# powermeter.net
KiCad netlist of a schematic drawn in EAGLE
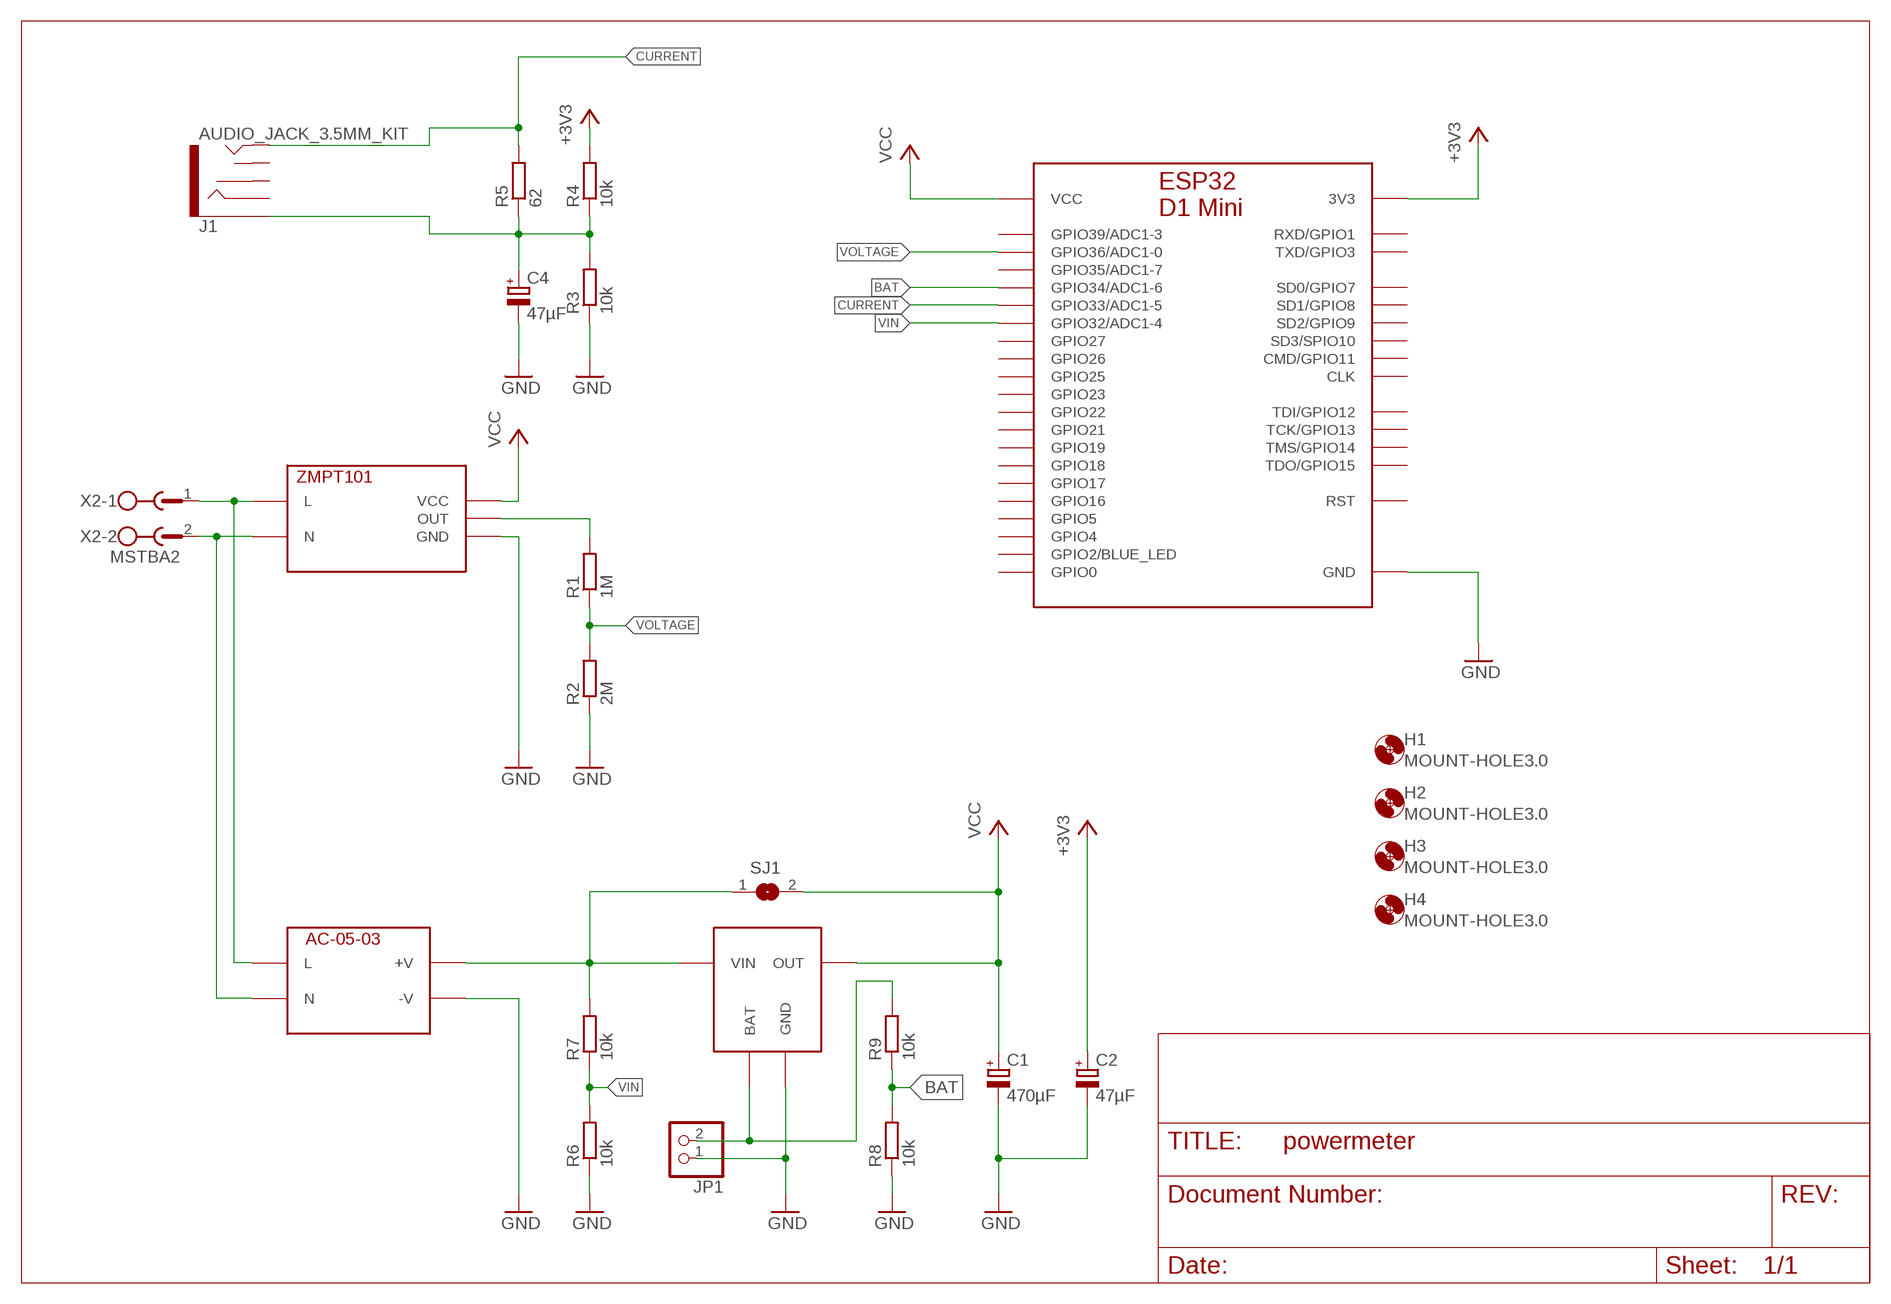
[diagram p0: schematic, sheet 1]

(export (version "E")
  (design (tool "Eeschema 10.0.6"))
  (components
    (comp (ref "C1")
      (value "470µF")
      (footprint "eagle-import:E5-8,5")
      (libsource (lib "eagle-import") (part "CPOL-EUE5-8.5"))
    )
    (comp (ref "C2")
      (value "47µF")
      (footprint "eagle-import:E2,5-5")
      (libsource (lib "eagle-import") (part "CPOL-EUE2.5-5"))
    )
    (comp (ref "C4")
      (value "47µF")
      (footprint "eagle-import:E2,5-5")
      (libsource (lib "eagle-import") (part "CPOL-EUE2.5-5"))
    )
    (comp (ref "H1")
      (value "MOUNT-HOLE3.0")
      (footprint "eagle-import:3,0")
      (libsource (lib "eagle-import") (part "MOUNT-HOLE3.0"))
    )
    (comp (ref "H2")
      (value "MOUNT-HOLE3.0")
      (footprint "eagle-import:3,0")
      (libsource (lib "eagle-import") (part "MOUNT-HOLE3.0"))
    )
    (comp (ref "H3")
      (value "MOUNT-HOLE3.0")
      (footprint "eagle-import:3,0")
      (libsource (lib "eagle-import") (part "MOUNT-HOLE3.0"))
    )
    (comp (ref "H4")
      (value "MOUNT-HOLE3.0")
      (footprint "eagle-import:3,0")
      (libsource (lib "eagle-import") (part "MOUNT-HOLE3.0"))
    )
    (comp (ref "J1")
      (value "AUDIO_JACK_3.5MM_KIT")
      (footprint "eagle-import:AUDIO-JACK-KIT")
      (libsource (lib "eagle-import") (part "AUDIO_JACK_3.5MM_KIT"))
    )
    (comp (ref "JP1")
      (value "PINHD-1X2")
      (footprint "eagle-import:1X02")
      (libsource (lib "eagle-import") (part "PINHD-1X2"))
    )
    (comp (ref "R1")
      (value "1M")
      (footprint "eagle-import:0204_7")
      (libsource (lib "eagle-import") (part "R-EU_0204/7"))
    )
    (comp (ref "R2")
      (value "2M")
      (footprint "eagle-import:0204_7")
      (libsource (lib "eagle-import") (part "R-EU_0204/7"))
    )
    (comp (ref "R3")
      (value "10k")
      (footprint "eagle-import:0204_7")
      (libsource (lib "eagle-import") (part "R-EU_0204/7"))
    )
    (comp (ref "R4")
      (value "10k")
      (footprint "eagle-import:0204_7")
      (libsource (lib "eagle-import") (part "R-EU_0204/7"))
    )
    (comp (ref "R5")
      (value "62")
      (footprint "eagle-import:0204_7")
      (libsource (lib "eagle-import") (part "R-EU_0204/7"))
    )
    (comp (ref "R6")
      (value "10k")
      (footprint "eagle-import:0204_7")
      (libsource (lib "eagle-import") (part "R-EU_0204/7"))
    )
    (comp (ref "R7")
      (value "10k")
      (footprint "eagle-import:0204_7")
      (libsource (lib "eagle-import") (part "R-EU_0204/7"))
    )
    (comp (ref "R8")
      (value "10k")
      (footprint "eagle-import:0204_7")
      (libsource (lib "eagle-import") (part "R-EU_0204/7"))
    )
    (comp (ref "R9")
      (value "10k")
      (footprint "eagle-import:0204_7")
      (libsource (lib "eagle-import") (part "R-EU_0204/7"))
    )
    (comp (ref "SJ1") (value "SJ") (footprint "eagle-import:SJ") (libsource (lib "eagle-import") (part "SJ")))
    (comp (ref "U$1")
      (value "ZMPT101")
      (footprint "eagle-import:ZMPT101")
      (libsource (lib "eagle-import") (part "ZMPT101"))
    )
    (comp (ref "U$2")
      (value "AC-05-03")
      (footprint "eagle-import:AC-05-03")
      (libsource (lib "eagle-import") (part "AC-05-03"))
    )
    (comp (ref "U$3")
      (value "MINI-UPS-S")
      (footprint "eagle-import:MINI-UPS-S")
      (libsource (lib "eagle-import") (part "MINI-UPS-S"))
    )
    (comp (ref "U1")
      (value "ESP32D1MINI")
      (footprint "eagle-import:ESP32D1MINI")
      (libsource (lib "eagle-import") (part "ESP32D1MINI"))
    )
    (comp (ref "X2")
      (value "MSTBA2")
      (footprint "eagle-import:MSTBA2")
      (fields (field (name "MF") "FARNELL") (field (name "MPN") "1757242"))
      (libsource (lib "eagle-import") (part "MSTBA2"))
    )
  )
  (nets
    (net (code "1") (name "+3V3") (class "Default")
      (node (ref "C2") (pin "+") (pinfunction "+_+") (pintype "passive"))
      (node (ref "R4") (pin "2") (pinfunction "2_2") (pintype "passive"))
      (node (ref "U1") (pin "3V3") (pinfunction "3V3_3V3") (pintype "power_in"))
    )
    (net (code "2") (name "BAT") (class "Default")
      (node (ref "R8") (pin "2") (pinfunction "2_2") (pintype "passive"))
      (node (ref "R9") (pin "1") (pinfunction "1_1") (pintype "passive"))
      (node (ref "U1") (pin "IO34") (pinfunction "GPIO34/ADC1-6_IO34") (pintype "bidirectional"))
    )
    (net (code "3") (name "CURRENT") (class "Default")
      (node (ref "J1") (pin "TIP") (pinfunction "TIP_TIP") (pintype "bidirectional"))
      (node (ref "R5") (pin "2") (pinfunction "2_2") (pintype "passive"))
      (node (ref "U1") (pin "IO33") (pinfunction "GPIO33/ADC1-5_IO33") (pintype "bidirectional"))
    )
    (net (code "4") (name "GND") (class "Default")
      (node (ref "C1") (pin "-") (pinfunction "-_-") (pintype "passive"))
      (node (ref "C2") (pin "-") (pinfunction "-_-") (pintype "passive"))
      (node (ref "C4") (pin "-") (pinfunction "-_-") (pintype "passive"))
      (node (ref "JP1") (pin "1") (pinfunction "1_1") (pintype "passive"))
      (node (ref "R2") (pin "1") (pinfunction "1_1") (pintype "passive"))
      (node (ref "R3") (pin "1") (pinfunction "1_1") (pintype "passive"))
      (node (ref "R6") (pin "1") (pinfunction "1_1") (pintype "passive"))
      (node (ref "R8") (pin "1") (pinfunction "1_1") (pintype "passive"))
      (node (ref "U$1") (pin "P$3") (pinfunction "GND_P$3") (pintype "power_in"))
      (node (ref "U$1") (pin "P$4") (pinfunction "GND_P$4") (pintype "power_in"))
      (node (ref "U$2") (pin "-V") (pinfunction "-V_-V") (pintype "output"))
      (node (ref "U$3") (pin "P$1") (pinfunction "GND_P$1") (pintype "power_in"))
      (node (ref "U$3") (pin "P$3") (pinfunction "GND_P$3") (pintype "power_in"))
      (node (ref "U$3") (pin "P$4") (pinfunction "GND_P$4") (pintype "power_in"))
      (node (ref "U1") (pin "GND1") (pinfunction "GND_GND1") (pintype "power_in"))
      (node (ref "U1") (pin "GND2") (pinfunction "GND_GND2") (pintype "power_in"))
      (node (ref "U1") (pin "GND3") (pinfunction "GND_GND3") (pintype "power_in"))
    )
    (net (code "5") (name "Net-(C4-Pad+)") (class "Default")
      (node (ref "C4") (pin "+") (pinfunction "+_+") (pintype "passive"))
      (node (ref "J1") (pin "SLEEVE") (pinfunction "SLEEVE_SLEEVE") (pintype "bidirectional"))
      (node (ref "R3") (pin "2") (pinfunction "2_2") (pintype "passive"))
      (node (ref "R4") (pin "1") (pinfunction "1_1") (pintype "passive"))
      (node (ref "R5") (pin "1") (pinfunction "1_1") (pintype "passive"))
    )
    (net (code "6") (name "Net-(JP1-Pad2)") (class "Default")
      (node (ref "JP1") (pin "2") (pinfunction "2_2") (pintype "passive"))
      (node (ref "R9") (pin "2") (pinfunction "2_2") (pintype "passive"))
      (node (ref "U$3") (pin "BAT") (pinfunction "BAT_BAT") (pintype "power_in"))
    )
    (net (code "7") (name "Net-(R1-Pad2)") (class "Default")
      (node (ref "R1") (pin "2") (pinfunction "2_2") (pintype "passive"))
      (node (ref "U$1") (pin "OUT") (pinfunction "OUT_OUT") (pintype "output"))
    )
    (net (code "8") (name "Net-(R7-Pad2)") (class "Default")
      (node (ref "R7") (pin "2") (pinfunction "2_2") (pintype "passive"))
      (node (ref "SJ1") (pin "1") (pinfunction "1_1") (pintype "passive"))
      (node (ref "U$2") (pin "+V") (pinfunction "+V_+V") (pintype "output"))
      (node (ref "U$3") (pin "VIN") (pinfunction "VIN_VIN") (pintype "power_in"))
    )
    (net (code "9") (name "Net-(U$1-PadL)") (class "Default")
      (node (ref "U$1") (pin "L") (pinfunction "L_L") (pintype "input"))
      (node (ref "U$2") (pin "L") (pinfunction "L_L") (pintype "input"))
      (node (ref "X2") (pin "1") (pinfunction "1_1") (pintype "passive"))
    )
    (net (code "10") (name "Net-(X2B-1)") (class "Default")
      (node (ref "U$1") (pin "N") (pinfunction "N_N") (pintype "input"))
      (node (ref "U$2") (pin "N") (pinfunction "N_N") (pintype "input"))
      (node (ref "X2") (pin "2") (pinfunction "1_2") (pintype "passive"))
    )
    (net (code "11") (name "VCC") (class "Default")
      (node (ref "C1") (pin "+") (pinfunction "+_+") (pintype "passive"))
      (node (ref "SJ1") (pin "2") (pinfunction "2_2") (pintype "passive"))
      (node (ref "U$1") (pin "VCC") (pinfunction "VCC_VCC") (pintype "power_in"))
      (node (ref "U$3") (pin "OUT") (pinfunction "OUT_OUT") (pintype "power_in"))
      (node (ref "U1") (pin "VCC") (pinfunction "VCC_VCC") (pintype "power_in"))
    )
    (net (code "12") (name "VIN") (class "Default")
      (node (ref "R6") (pin "2") (pinfunction "2_2") (pintype "passive"))
      (node (ref "R7") (pin "1") (pinfunction "1_1") (pintype "passive"))
      (node (ref "U1") (pin "IO32") (pinfunction "GPIO32/ADC1-4_IO32") (pintype "bidirectional"))
    )
    (net (code "13") (name "VOLTAGE") (class "Default")
      (node (ref "R1") (pin "1") (pinfunction "1_1") (pintype "passive"))
      (node (ref "R2") (pin "2") (pinfunction "2_2") (pintype "passive"))
      (node (ref "U1") (pin "IO36") (pinfunction "GPIO36/ADC1-0_IO36") (pintype "bidirectional"))
    )
    (net (code "14") (name "unconnected-(J1-PadRING)") (class "Default")
      (node (ref "J1") (pin "RING") (pinfunction "RING_RING") (pintype "bidirectional"))
    )
    (net (code "15") (name "unconnected-(J1-PadRSH)") (class "Default")
      (node (ref "J1") (pin "RSH") (pinfunction "RSH_RSH") (pintype "bidirectional"))
    )
    (net (code "16") (name "unconnected-(J1-PadTSH)") (class "Default")
      (node (ref "J1") (pin "TSH") (pinfunction "TSH_TSH") (pintype "bidirectional"))
    )
    (net (code "17") (name "unconnected-(U1-CMD{slash}GPIO11-PadCMD)") (class "Default")
      (node (ref "U1") (pin "CMD") (pinfunction "CMD/GPIO11_CMD") (pintype "bidirectional"))
    )
    (net (code "18") (name "unconnected-(U1-GPIO0-PadIO0)") (class "Default")
      (node (ref "U1") (pin "IO0") (pinfunction "GPIO0_IO0") (pintype "input"))
    )
    (net (code "19") (name "unconnected-(U1-GPIO2{slash}BLUE_LED-PadIO2)") (class "Default")
      (node (ref "U1") (pin "IO2") (pinfunction "GPIO2/BLUE_LED_IO2") (pintype "bidirectional"))
    )
    (net (code "20") (name "unconnected-(U1-GPIO4-PadIO4)") (class "Default")
      (node (ref "U1") (pin "IO4") (pinfunction "GPIO4_IO4") (pintype "bidirectional"))
    )
    (net (code "21") (name "unconnected-(U1-GPIO5-PadIO5)") (class "Default")
      (node (ref "U1") (pin "IO5") (pinfunction "GPIO5_IO5") (pintype "bidirectional"))
    )
    (net (code "22") (name "unconnected-(U1-GPIO16-PadIO16)") (class "Default")
      (node (ref "U1") (pin "IO16") (pinfunction "GPIO16_IO16") (pintype "bidirectional"))
    )
    (net (code "23") (name "unconnected-(U1-GPIO17-PadIO17)") (class "Default")
      (node (ref "U1") (pin "IO17") (pinfunction "GPIO17_IO17") (pintype "bidirectional"))
    )
    (net (code "24") (name "unconnected-(U1-GPIO18-PadIO18)") (class "Default")
      (node (ref "U1") (pin "IO18") (pinfunction "GPIO18_IO18") (pintype "bidirectional"))
    )
    (net (code "25") (name "unconnected-(U1-GPIO19-PadIO19)") (class "Default")
      (node (ref "U1") (pin "IO19") (pinfunction "GPIO19_IO19") (pintype "bidirectional"))
    )
    (net (code "26") (name "unconnected-(U1-GPIO21-PadIO21)") (class "Default")
      (node (ref "U1") (pin "IO21") (pinfunction "GPIO21_IO21") (pintype "bidirectional"))
    )
    (net (code "27") (name "unconnected-(U1-GPIO22-PadIO22)") (class "Default")
      (node (ref "U1") (pin "IO22") (pinfunction "GPIO22_IO22") (pintype "bidirectional"))
    )
    (net (code "28") (name "unconnected-(U1-GPIO23-PadIO23)") (class "Default")
      (node (ref "U1") (pin "IO23") (pinfunction "GPIO23_IO23") (pintype "bidirectional"))
    )
    (net (code "29") (name "unconnected-(U1-GPIO25-PadIO25)") (class "Default")
      (node (ref "U1") (pin "IO25") (pinfunction "GPIO25_IO25") (pintype "bidirectional"))
    )
    (net (code "30") (name "unconnected-(U1-GPIO26-PadIO26)") (class "Default")
      (node (ref "U1") (pin "IO26") (pinfunction "GPIO26_IO26") (pintype "bidirectional"))
    )
    (net (code "31") (name "unconnected-(U1-GPIO27-PadIO27)") (class "Default")
      (node (ref "U1") (pin "IO27") (pinfunction "GPIO27_IO27") (pintype "bidirectional"))
    )
    (net (code "32") (name "unconnected-(U1-GPIO35{slash}ADC1-7-PadIO35)") (class "Default")
      (node (ref "U1") (pin "IO35") (pinfunction "GPIO35/ADC1-7_IO35") (pintype "bidirectional"))
    )
    (net (code "33") (name "unconnected-(U1-GPIO39{slash}ADC1-3-PadIO39)") (class "Default")
      (node (ref "U1") (pin "IO39") (pinfunction "GPIO39/ADC1-3_IO39") (pintype "bidirectional"))
    )
    (net (code "34") (name "unconnected-(U1-PadCLK)") (class "Default")
      (node (ref "U1") (pin "CLK") (pinfunction "CLK_CLK") (pintype "bidirectional"))
    )
    (net (code "35") (name "unconnected-(U1-PadRST)") (class "Default")
      (node (ref "U1") (pin "RST") (pinfunction "RST_RST") (pintype "input"))
    )
    (net (code "36") (name "unconnected-(U1-RXD{slash}GPIO1-PadRXD)") (class "Default")
      (node (ref "U1") (pin "RXD") (pinfunction "RXD/GPIO1_RXD") (pintype "input"))
    )
    (net (code "37") (name "unconnected-(U1-SD0{slash}GPIO7-PadSD0)") (class "Default")
      (node (ref "U1") (pin "SD0") (pinfunction "SD0/GPIO7_SD0") (pintype "bidirectional"))
    )
    (net (code "38") (name "unconnected-(U1-SD1{slash}GPIO8-PadSD1)") (class "Default")
      (node (ref "U1") (pin "SD1") (pinfunction "SD1/GPIO8_SD1") (pintype "bidirectional"))
    )
    (net (code "39") (name "unconnected-(U1-SD2{slash}GPIO9-PadSD2)") (class "Default")
      (node (ref "U1") (pin "SD2") (pinfunction "SD2/GPIO9_SD2") (pintype "bidirectional"))
    )
    (net (code "40") (name "unconnected-(U1-SD3{slash}SPIO10-PadSD3)") (class "Default")
      (node (ref "U1") (pin "SD3") (pinfunction "SD3/SPIO10_SD3") (pintype "bidirectional"))
    )
    (net (code "41") (name "unconnected-(U1-TCK{slash}GPIO13-PadTCK)") (class "Default")
      (node (ref "U1") (pin "TCK") (pinfunction "TCK/GPIO13_TCK") (pintype "bidirectional"))
    )
    (net (code "42") (name "unconnected-(U1-TDI{slash}GPIO12-PadTDI)") (class "Default")
      (node (ref "U1") (pin "TDI") (pinfunction "TDI/GPIO12_TDI") (pintype "bidirectional"))
    )
    (net (code "43") (name "unconnected-(U1-TDO{slash}GPIO15-PadTDO)") (class "Default")
      (node (ref "U1") (pin "TDO") (pinfunction "TDO/GPIO15_TDO") (pintype "bidirectional"))
    )
    (net (code "44") (name "unconnected-(U1-TMS{slash}GPIO14-PadTMS)") (class "Default")
      (node (ref "U1") (pin "TMS") (pinfunction "TMS/GPIO14_TMS") (pintype "bidirectional"))
    )
    (net (code "45") (name "unconnected-(U1-TXD{slash}GPIO3-PadTXD)") (class "Default")
      (node (ref "U1") (pin "TXD") (pinfunction "TXD/GPIO3_TXD") (pintype "bidirectional"))
    )
  )
)
